# POT_1_0.net
KiCad netlist of a schematic drawn in EAGLE
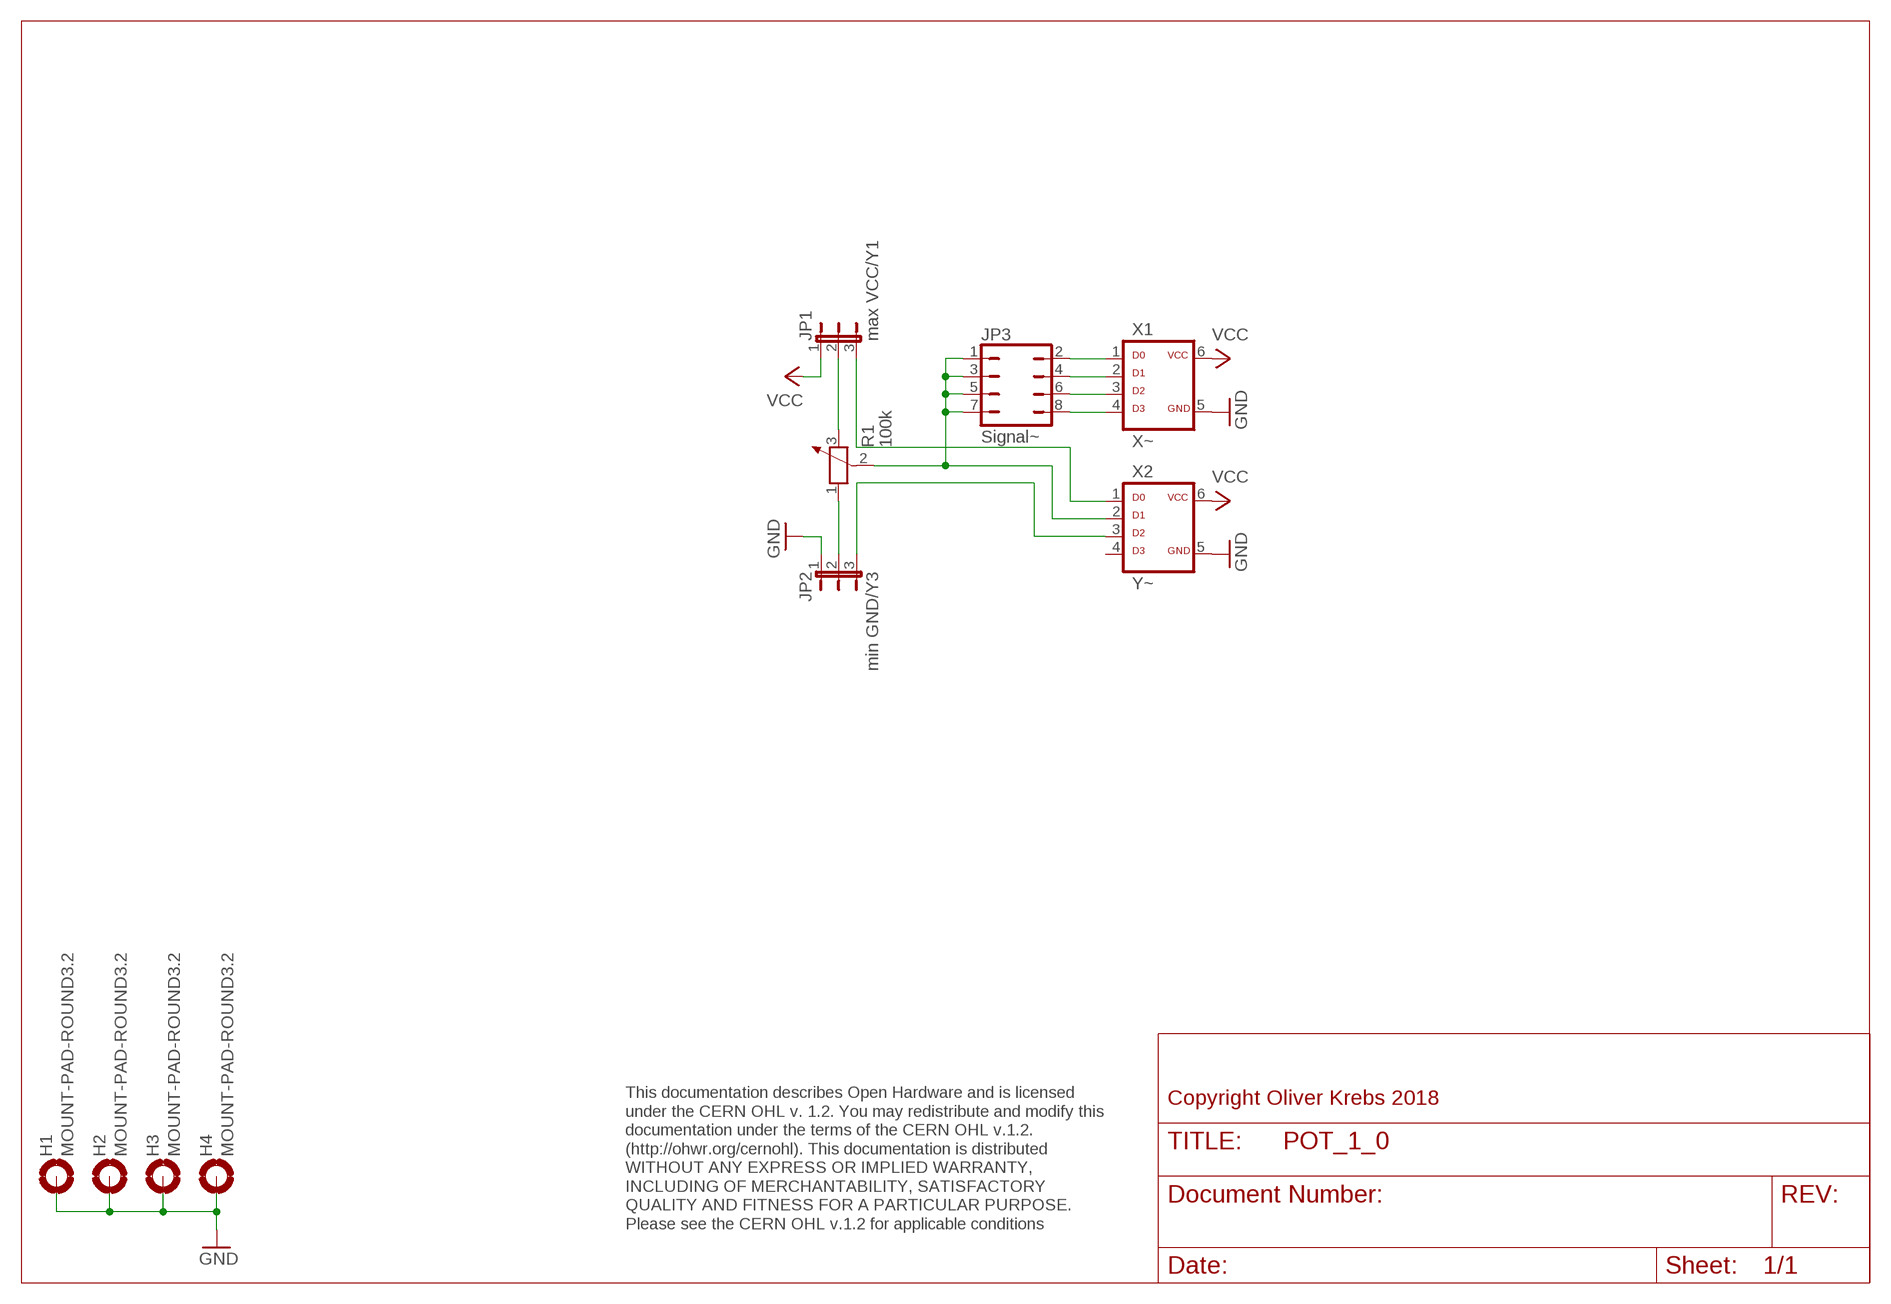
[diagram p0: schematic, sheet 1]

(export (version "E")
  (design (tool "Eeschema 10.0.6"))
  (components
    (comp (ref "H1")
      (value "MOUNT-PAD-ROUND3.2")
      (footprint "eagle-import:3,2-PAD")
      (libsource (lib "eagle-import") (part "MOUNT-PAD-ROUND3.2"))
    )
    (comp (ref "H2")
      (value "MOUNT-PAD-ROUND3.2")
      (footprint "eagle-import:3,2-PAD")
      (libsource (lib "eagle-import") (part "MOUNT-PAD-ROUND3.2"))
    )
    (comp (ref "H3")
      (value "MOUNT-PAD-ROUND3.2")
      (footprint "eagle-import:3,2-PAD")
      (libsource (lib "eagle-import") (part "MOUNT-PAD-ROUND3.2"))
    )
    (comp (ref "H4")
      (value "MOUNT-PAD-ROUND3.2")
      (footprint "eagle-import:3,2-PAD")
      (libsource (lib "eagle-import") (part "MOUNT-PAD-ROUND3.2"))
    )
    (comp (ref "JP1")
      (value "max VCC/Y1")
      (footprint "eagle-import:JP2-U")
      (libsource (lib "eagle-import") (part "JP2EJP2-U"))
    )
    (comp (ref "JP2")
      (value "min GND/Y3")
      (footprint "eagle-import:JP2-U")
      (libsource (lib "eagle-import") (part "JP2EJP2-U"))
    )
    (comp (ref "JP3")
      (value "Signal~")
      (footprint "eagle-import:JP4Q")
      (libsource (lib "eagle-import") (part "JP4Q"))
    )
    (comp (ref "R1")
      (value "100k")
      (footprint "eagle-import:RK09K113")
      (libsource (lib "eagle-import") (part "POTENTIOMETER_RK09K113"))
    )
    (comp (ref "X1")
      (value "X~")
      (footprint "eagle-import:ML-6")
      (libsource (lib "eagle-import") (part "ML6D"))
    )
    (comp (ref "X2")
      (value "Y~")
      (footprint "eagle-import:ML-6")
      (libsource (lib "eagle-import") (part "ML6D"))
    )
  )
  (nets
    (net (code "1") (name "GND") (class "Default")
      (node (ref "H1") (pin "B3,2") (pinfunction "MOUNT_B3,2") (pintype "passive"))
      (node (ref "H2") (pin "B3,2") (pinfunction "MOUNT_B3,2") (pintype "passive"))
      (node (ref "H3") (pin "B3,2") (pinfunction "MOUNT_B3,2") (pintype "passive"))
      (node (ref "H4") (pin "B3,2") (pinfunction "MOUNT_B3,2") (pintype "passive"))
      (node (ref "JP2") (pin "1") (pinfunction "1_1") (pintype "passive"))
      (node (ref "X1") (pin "5") (pinfunction "5_5") (pintype "passive"))
      (node (ref "X2") (pin "5") (pinfunction "5_5") (pintype "passive"))
    )
    (net (code "2") (name "Net-(JP1-Pad3)") (class "Default")
      (node (ref "JP1") (pin "3") (pinfunction "3_3") (pintype "passive"))
      (node (ref "X2") (pin "1") (pinfunction "1_1") (pintype "passive"))
    )
    (net (code "3") (name "Net-(JP2-Pad2)") (class "Default")
      (node (ref "JP2") (pin "2") (pinfunction "2_2") (pintype "passive"))
      (node (ref "R1") (pin "1") (pinfunction "1_1") (pintype "passive"))
    )
    (net (code "4") (name "Net-(JP2-Pad3)") (class "Default")
      (node (ref "JP2") (pin "3") (pinfunction "3_3") (pintype "passive"))
      (node (ref "X2") (pin "3") (pinfunction "3_3") (pintype "passive"))
    )
    (net (code "5") (name "Net-(JP3-Pad2)") (class "Default")
      (node (ref "JP3") (pin "2") (pinfunction "2_2") (pintype "passive"))
      (node (ref "X1") (pin "1") (pinfunction "1_1") (pintype "passive"))
    )
    (net (code "6") (name "Net-(JP3-Pad4)") (class "Default")
      (node (ref "JP3") (pin "4") (pinfunction "4_4") (pintype "passive"))
      (node (ref "X1") (pin "2") (pinfunction "2_2") (pintype "passive"))
    )
    (net (code "7") (name "Net-(JP3-Pad6)") (class "Default")
      (node (ref "JP3") (pin "6") (pinfunction "6_6") (pintype "passive"))
      (node (ref "X1") (pin "3") (pinfunction "3_3") (pintype "passive"))
    )
    (net (code "8") (name "Net-(JP3-Pad8)") (class "Default")
      (node (ref "JP3") (pin "8") (pinfunction "8_8") (pintype "passive"))
      (node (ref "X1") (pin "4") (pinfunction "4_4") (pintype "passive"))
    )
    (net (code "9") (name "Net-(R1-2)") (class "Default")
      (node (ref "JP1") (pin "2") (pinfunction "2_2") (pintype "passive"))
      (node (ref "R1") (pin "3") (pinfunction "2_3") (pintype "passive"))
    )
    (net (code "10") (name "Net-(R1-3)") (class "Default")
      (node (ref "JP3") (pin "1") (pinfunction "1_1") (pintype "passive"))
      (node (ref "JP3") (pin "3") (pinfunction "3_3") (pintype "passive"))
      (node (ref "JP3") (pin "5") (pinfunction "5_5") (pintype "passive"))
      (node (ref "JP3") (pin "7") (pinfunction "7_7") (pintype "passive"))
      (node (ref "R1") (pin "2") (pinfunction "3_2") (pintype "passive"))
      (node (ref "X2") (pin "2") (pinfunction "2_2") (pintype "passive"))
    )
    (net (code "11") (name "VCC") (class "Default")
      (node (ref "JP1") (pin "1") (pinfunction "1_1") (pintype "passive"))
      (node (ref "X1") (pin "6") (pinfunction "6_6") (pintype "passive"))
      (node (ref "X2") (pin "6") (pinfunction "6_6") (pintype "passive"))
    )
    (net (code "12") (name "unconnected-(X2-Pad4)") (class "Default")
      (node (ref "X2") (pin "4") (pinfunction "4_4") (pintype "passive"))
    )
  )
)
